# EMS_esp32_wifi_v2_2.net
KiCad netlist of a schematic drawn in EAGLE
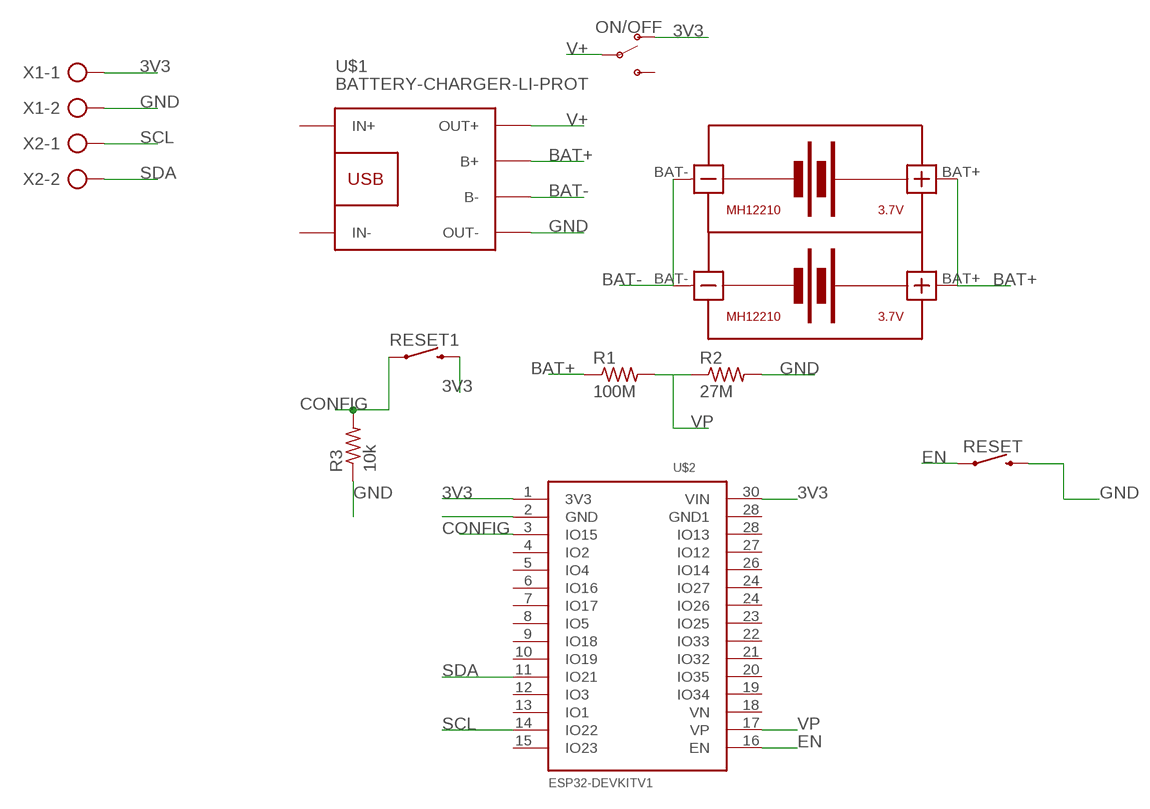
[diagram p0: schematic, sheet 1]

(export (version "E")
  (design (tool "Eeschema 10.0.6"))
  (components
    (comp (ref "ON/OFF")
      (value "SWITCH-SPDT-PTH-11.6X4.0MM")
      (footprint "eagle-import:SWITCH_SPDT_PTH_11.6X4.0MM")
      (libsource (lib "eagle-import") (part "SWITCH-SPDT-PTH-11.6X4.0MM"))
    )
    (comp (ref "R1")
      (value "100M")
      (footprint "eagle-import:0204_7")
      (libsource (lib "eagle-import") (part "R-US_0204/7"))
    )
    (comp (ref "R2")
      (value "27M")
      (footprint "eagle-import:0204_7")
      (libsource (lib "eagle-import") (part "R-US_0204/7"))
    )
    (comp (ref "R3")
      (value "10k")
      (footprint "eagle-import:0204_7")
      (libsource (lib "eagle-import") (part "R-US_0204/7"))
    )
    (comp (ref "RESET")
      (value "MOMENTARY-SWITCH-SPST-PTH-6.0MM")
      (footprint "eagle-import:TACTILE_SWITCH_PTH_6.0MM")
      (libsource (lib "eagle-import") (part "MOMENTARY-SWITCH-SPST-PTH-6.0MM"))
    )
    (comp (ref "RESET1")
      (value "MOMENTARY-SWITCH-SPST-PTH-6.0MM")
      (footprint "eagle-import:TACTILE_SWITCH_PTH_6.0MM")
      (libsource (lib "eagle-import") (part "MOMENTARY-SWITCH-SPST-PTH-6.0MM"))
    )
    (comp (ref "U$1")
      (value "BATTERY-CHARGER-LI-PROT")
      (footprint "eagle-import:BATTERY-CHARGER-LI-PROT")
      (libsource (lib "eagle-import") (part "BATTERY-CHARGER-LI-PROT"))
    )
    (comp (ref "U$2")
      (value "ESP32DEVKITV1")
      (footprint "eagle-import:ESP32-DEVKITV1")
      (libsource (lib "eagle-import") (part "ESP32DEVKITV1"))
    )
    (comp (ref "U$3")
      (value "BATTERY-LI-MH12210")
      (footprint "eagle-import:BATTERY-LI-MH12210")
      (libsource (lib "eagle-import") (part "BATTERY-LI-MH12210"))
    )
    (comp (ref "U$4")
      (value "BATTERY-LI-MH12210")
      (footprint "eagle-import:BATTERY-LI-MH12210")
      (libsource (lib "eagle-import") (part "BATTERY-LI-MH12210"))
    )
    (comp (ref "X1")
      (value "AK500/2")
      (footprint "eagle-import:AK500_2")
      (libsource (lib "eagle-import") (part "AK500/2"))
    )
    (comp (ref "X2")
      (value "AK500/2")
      (footprint "eagle-import:AK500_2")
      (libsource (lib "eagle-import") (part "AK500/2"))
    )
  )
  (nets
    (net (code "1") (name "/3V3") (class "Default")
      (node (ref "ON/OFF") (pin "1") (pinfunction "O_1") (pintype "passive"))
      (node (ref "RESET1") (pin "3") (pinfunction "2_3") (pintype "passive"))
      (node (ref "U$2") (pin "1") (pinfunction "3V3_1") (pintype "bidirectional"))
      (node (ref "U$2") (pin "30") (pinfunction "VIN_30") (pintype "bidirectional"))
      (node (ref "X1") (pin "1") (pinfunction "KL_1") (pintype "passive"))
    )
    (net (code "2") (name "/BAT+") (class "Default")
      (node (ref "R1") (pin "1") (pinfunction "1_1") (pintype "passive"))
      (node (ref "U$1") (pin "B+") (pinfunction "B+_B+") (pintype "bidirectional"))
      (node (ref "U$3") (pin "BAT+") (pinfunction "BAT+_BAT+") (pintype "power_in"))
      (node (ref "U$4") (pin "BAT+") (pinfunction "BAT+_BAT+") (pintype "power_in"))
    )
    (net (code "3") (name "/BAT-") (class "Default")
      (node (ref "U$1") (pin "B-") (pinfunction "B-_B-") (pintype "bidirectional"))
      (node (ref "U$3") (pin "BAT-") (pinfunction "BAT-_BAT-") (pintype "power_in"))
      (node (ref "U$4") (pin "BAT-") (pinfunction "BAT-_BAT-") (pintype "power_in"))
    )
    (net (code "4") (name "/CONFIG") (class "Default")
      (node (ref "R3") (pin "2") (pinfunction "2_2") (pintype "passive"))
      (node (ref "RESET1") (pin "1") (pinfunction "1_1") (pintype "passive"))
      (node (ref "U$2") (pin "3") (pinfunction "IO15_3") (pintype "bidirectional"))
    )
    (net (code "5") (name "/EN") (class "Default")
      (node (ref "RESET") (pin "1") (pinfunction "1_1") (pintype "passive"))
      (node (ref "U$2") (pin "16") (pinfunction "EN_16") (pintype "bidirectional"))
    )
    (net (code "6") (name "/GND") (class "Default")
      (node (ref "R2") (pin "2") (pinfunction "2_2") (pintype "passive"))
      (node (ref "R3") (pin "1") (pinfunction "1_1") (pintype "passive"))
      (node (ref "RESET") (pin "3") (pinfunction "2_3") (pintype "passive"))
      (node (ref "U$1") (pin "OUT-") (pinfunction "OUT-_OUT-") (pintype "bidirectional"))
      (node (ref "U$2") (pin "2") (pinfunction "GND_2") (pintype "bidirectional"))
      (node (ref "X1") (pin "2") (pinfunction "KL_2") (pintype "passive"))
    )
    (net (code "7") (name "/SCL") (class "Default")
      (node (ref "U$2") (pin "14") (pinfunction "IO22_14") (pintype "bidirectional"))
      (node (ref "X2") (pin "1") (pinfunction "KL_1") (pintype "passive"))
    )
    (net (code "8") (name "/SDA") (class "Default")
      (node (ref "U$2") (pin "11") (pinfunction "IO21_11") (pintype "bidirectional"))
      (node (ref "X2") (pin "2") (pinfunction "KL_2") (pintype "passive"))
    )
    (net (code "9") (name "/V+") (class "Default")
      (node (ref "ON/OFF") (pin "2") (pinfunction "P_2") (pintype "passive"))
      (node (ref "U$1") (pin "OUT+") (pinfunction "OUT+_OUT+") (pintype "bidirectional"))
    )
    (net (code "10") (name "/VP") (class "Default")
      (node (ref "R1") (pin "2") (pinfunction "2_2") (pintype "passive"))
      (node (ref "R2") (pin "1") (pinfunction "1_1") (pintype "passive"))
      (node (ref "U$2") (pin "17") (pinfunction "VP_17") (pintype "bidirectional"))
    )
    (net (code "11") (name "unconnected-(ON/OFF-S-Pad3)") (class "Default")
      (node (ref "ON/OFF") (pin "3") (pinfunction "S_3") (pintype "passive"))
    )
    (net (code "12") (name "unconnected-(U$1-PadIN+)") (class "Default")
      (node (ref "U$1") (pin "IN+") (pinfunction "IN+_IN+") (pintype "bidirectional"))
    )
    (net (code "13") (name "unconnected-(U$1-PadIN-)") (class "Default")
      (node (ref "U$1") (pin "IN-") (pinfunction "IN-_IN-") (pintype "bidirectional"))
    )
    (net (code "14") (name "unconnected-(U$2-GND1-Pad28)") (class "Default")
      (node (ref "U$2") (pin "28") (pinfunction "GND1_28") (pintype "bidirectional"))
    )
    (net (code "15") (name "unconnected-(U$2-IO1-Pad13)") (class "Default")
      (node (ref "U$2") (pin "13") (pinfunction "IO1_13") (pintype "bidirectional"))
    )
    (net (code "16") (name "unconnected-(U$2-IO2-Pad4)") (class "Default")
      (node (ref "U$2") (pin "4") (pinfunction "IO2_4") (pintype "bidirectional"))
    )
    (net (code "17") (name "unconnected-(U$2-IO3-Pad12)") (class "Default")
      (node (ref "U$2") (pin "12") (pinfunction "IO3_12") (pintype "bidirectional"))
    )
    (net (code "18") (name "unconnected-(U$2-IO4-Pad5)") (class "Default")
      (node (ref "U$2") (pin "5") (pinfunction "IO4_5") (pintype "bidirectional"))
    )
    (net (code "19") (name "unconnected-(U$2-IO5-Pad8)") (class "Default")
      (node (ref "U$2") (pin "8") (pinfunction "IO5_8") (pintype "bidirectional"))
    )
    (net (code "20") (name "unconnected-(U$2-IO12-Pad27)") (class "Default")
      (node (ref "U$2") (pin "27") (pinfunction "IO12_27") (pintype "bidirectional"))
    )
    (net (code "21") (name "unconnected-(U$2-IO13-Pad28)") (class "Default")
      (node (ref "U$2") (pin "28") (pinfunction "IO13_28") (pintype "bidirectional"))
    )
    (net (code "22") (name "unconnected-(U$2-IO14-Pad26)") (class "Default")
      (node (ref "U$2") (pin "26") (pinfunction "IO14_26") (pintype "bidirectional"))
    )
    (net (code "23") (name "unconnected-(U$2-IO16-Pad6)") (class "Default")
      (node (ref "U$2") (pin "6") (pinfunction "IO16_6") (pintype "bidirectional"))
    )
    (net (code "24") (name "unconnected-(U$2-IO17-Pad7)") (class "Default")
      (node (ref "U$2") (pin "7") (pinfunction "IO17_7") (pintype "bidirectional"))
    )
    (net (code "25") (name "unconnected-(U$2-IO18-Pad9)") (class "Default")
      (node (ref "U$2") (pin "9") (pinfunction "IO18_9") (pintype "bidirectional"))
    )
    (net (code "26") (name "unconnected-(U$2-IO19-Pad10)") (class "Default")
      (node (ref "U$2") (pin "10") (pinfunction "IO19_10") (pintype "bidirectional"))
    )
    (net (code "27") (name "unconnected-(U$2-IO23-Pad15)") (class "Default")
      (node (ref "U$2") (pin "15") (pinfunction "IO23_15") (pintype "bidirectional"))
    )
    (net (code "28") (name "unconnected-(U$2-IO25-Pad23)") (class "Default")
      (node (ref "U$2") (pin "23") (pinfunction "IO25_23") (pintype "bidirectional"))
    )
    (net (code "29") (name "unconnected-(U$2-IO26-Pad24)") (class "Default")
      (node (ref "U$2") (pin "24") (pinfunction "IO26_24") (pintype "bidirectional"))
    )
    (net (code "30") (name "unconnected-(U$2-IO27-Pad24)") (class "Default")
      (node (ref "U$2") (pin "24") (pinfunction "IO27_24") (pintype "bidirectional"))
    )
    (net (code "31") (name "unconnected-(U$2-IO32-Pad21)") (class "Default")
      (node (ref "U$2") (pin "21") (pinfunction "IO32_21") (pintype "bidirectional"))
    )
    (net (code "32") (name "unconnected-(U$2-IO33-Pad22)") (class "Default")
      (node (ref "U$2") (pin "22") (pinfunction "IO33_22") (pintype "bidirectional"))
    )
    (net (code "33") (name "unconnected-(U$2-IO34-Pad19)") (class "Default")
      (node (ref "U$2") (pin "19") (pinfunction "IO34_19") (pintype "bidirectional"))
    )
    (net (code "34") (name "unconnected-(U$2-IO35-Pad20)") (class "Default")
      (node (ref "U$2") (pin "20") (pinfunction "IO35_20") (pintype "bidirectional"))
    )
    (net (code "35") (name "unconnected-(U$2-VN-Pad18)") (class "Default")
      (node (ref "U$2") (pin "18") (pinfunction "VN_18") (pintype "bidirectional"))
    )
  )
)
